# Sheet1.net
KiCad netlist of a schematic drawn in Altium Designer
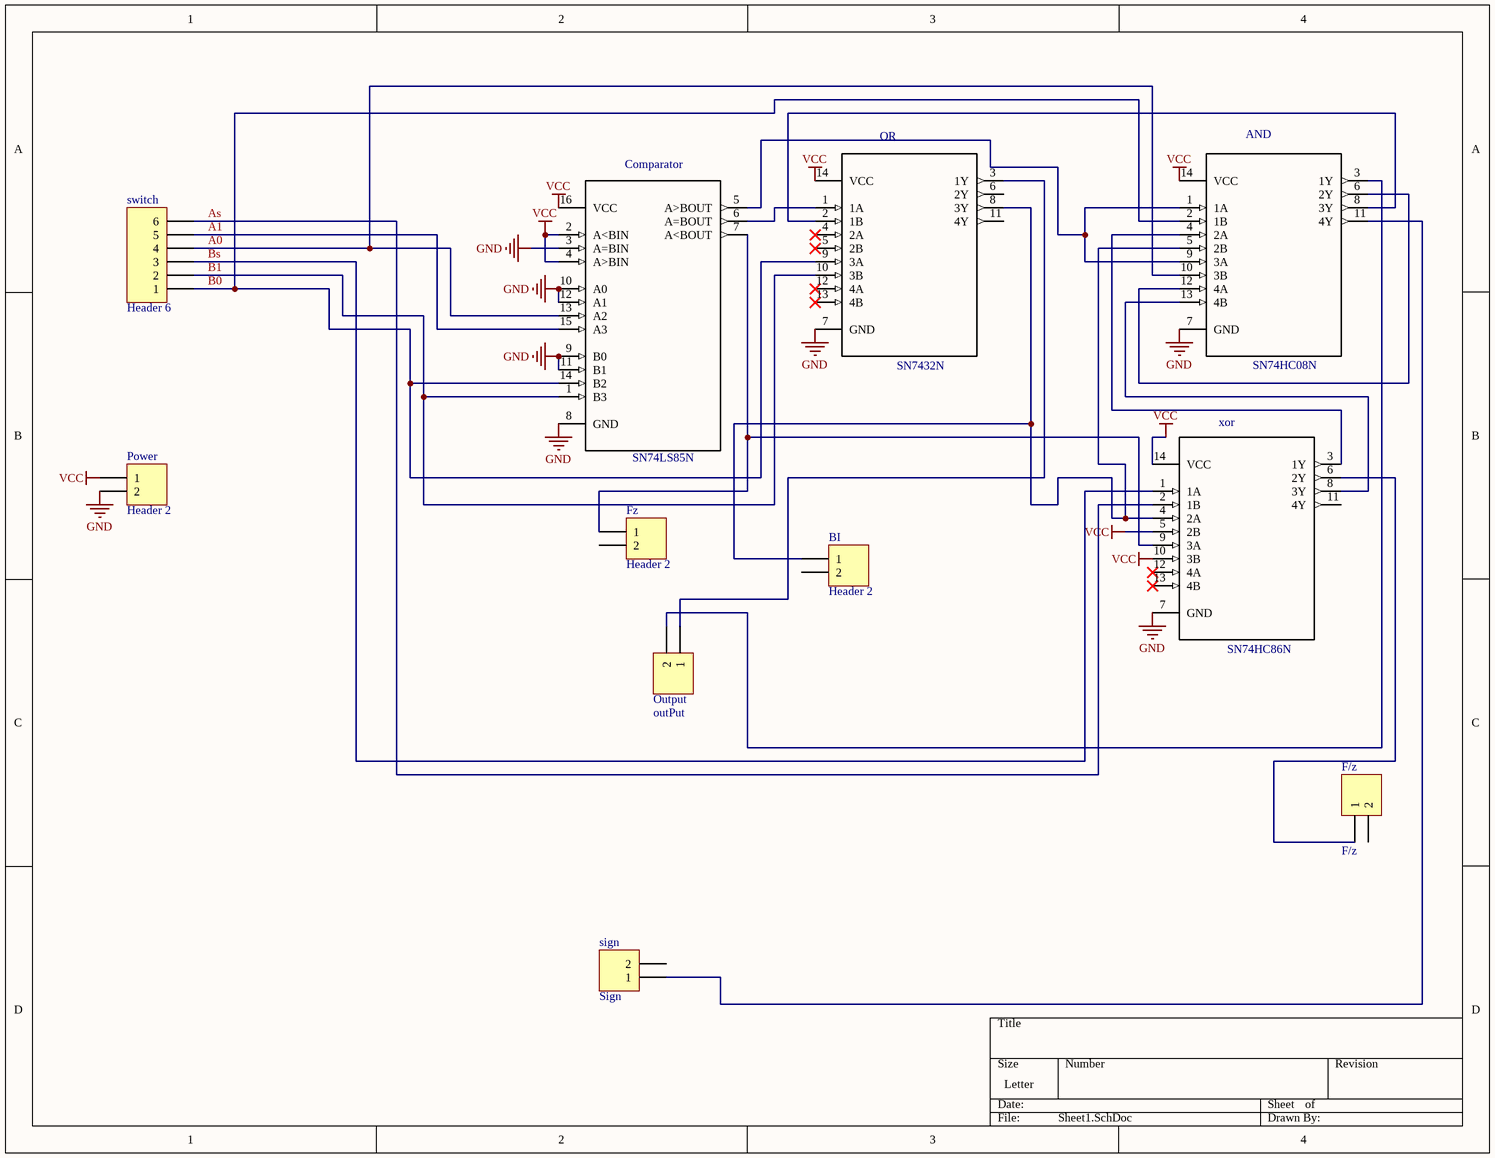
[diagram p0: Sheet1.SchDoc]

(export (version "E")
  (design (tool "Eeschema 10.0.6"))
  (components
    (comp (ref "AND")
      (value "SN74HC08N")
      (footprint "DIP254P762X508-14")
      (fields (field (name "MF") "Texas Instruments"))
      (libsource (lib "SN74HC08N") (part "SN74HC08N"))
    )
    (comp (ref "BI")
      (value "Header 2")
      (footprint "HDR1X2")
      (description "Header, 2-Pin")
      (fields (field (name "PUBLISHER") "Altium Limited"))
      (libsource (lib "Miscellaneous Connectors") (part "Header 2"))
    )
    (comp (ref "Comparator")
      (value "SN74LS85N")
      (footprint "DIP254P762X508-16")
      (description "Logic - Digital Comparators 4-bit binary or BCD Magnitude Comparator")
      (fields (field (name "MF") "Texas Instruments"))
      (libsource (lib "SN74LS85N") (part "SN74LS85N"))
    )
    (comp (ref "F/z")
      (value "F/z")
      (footprint "HDR1X2")
      (description "Header, 2-Pin")
      (fields (field (name "PUBLISHER") "Altium Limited"))
      (libsource (lib "") (part "Header 2_1"))
    )
    (comp (ref "Fz")
      (value "Header 2")
      (footprint "HDR1X2")
      (description "Header, 2-Pin")
      (fields (field (name "PUBLISHER") "Altium Limited"))
      (libsource (lib "Miscellaneous Connectors") (part "Header 2"))
    )
    (comp (ref "OR")
      (value "SN7432N")
      (footprint "DIP254P762X508-14")
      (description "OR Gate 4-Element 2-IN Bipolar 14-Pin PDIP Tube")
      (fields (field (name "MF") "Texas Instruments") (field (name "DIGI-KEY_PART_NUMBER") "296-33610-5-ND"))
      (libsource (lib "SN7432N") (part "SN7432N"))
    )
    (comp (ref "Output")
      (value "outPut")
      (footprint "HDR1X2")
      (description "Header, 2-Pin")
      (fields (field (name "PUBLISHER") "Altium Limited"))
      (libsource (lib "") (part "Header 2_2"))
    )
    (comp (ref "Power")
      (value "Header 2")
      (footprint "HDR1X2")
      (description "Header, 2-Pin")
      (fields (field (name "PUBLISHER") "Altium Limited"))
      (libsource (lib "Miscellaneous Connectors") (part "Header 2"))
    )
    (comp (ref "sign")
      (value "Sign")
      (footprint "HDR1X2")
      (description "Header, 2-Pin")
      (fields (field (name "PUBLISHER") "Altium Limited"))
      (libsource (lib "") (part "Header 2_3"))
    )
    (comp (ref "switch")
      (value "Header 6")
      (footprint "HDR1X6")
      (description "Header, 6-Pin")
      (fields (field (name "PUBLISHER") "Altium Limited"))
      (libsource (lib "Miscellaneous Connectors") (part "Header 6"))
    )
    (comp (ref "xor")
      (value "SN74HC86N")
      (footprint "DIP254P762X508-14")
      (description "IC: digital; inverter; XOR; Channels: 4; THT; DIP14; Series: HC")
      (fields (field (name "MF") "Texas Instruments"))
      (libsource (lib "SN74HC86N") (part "SN74HC86N"))
    )
  )
  (nets
    (net (code "1") (name "GND") (class "Default")
      (node (ref "AND") (pin "7") (pinfunction "GND_7") (pintype "passive"))
      (node (ref "Comparator") (pin "10") (pinfunction "A0_10") (pintype "input"))
      (node (ref "Comparator") (pin "11") (pinfunction "B1_11") (pintype "input"))
      (node (ref "Comparator") (pin "12") (pinfunction "A1_12") (pintype "input"))
      (node (ref "Comparator") (pin "3") (pinfunction "A=BIN_3") (pintype "input"))
      (node (ref "Comparator") (pin "8") (pinfunction "GND_8") (pintype "passive"))
      (node (ref "Comparator") (pin "9") (pinfunction "B0_9") (pintype "input"))
      (node (ref "OR") (pin "7") (pinfunction "GND_7") (pintype "passive"))
      (node (ref "Power") (pin "2") (pinfunction "2_2") (pintype "passive"))
      (node (ref "xor") (pin "7") (pinfunction "GND_7") (pintype "passive"))
    )
    (net (code "2") (name "Net-(AND-1A)") (class "Default")
      (node (ref "AND") (pin "1") (pinfunction "1A_1") (pintype "input"))
      (node (ref "AND") (pin "9") (pinfunction "3A_9") (pintype "input"))
      (node (ref "Comparator") (pin "5") (pinfunction "A>BOUT_5") (pintype "output"))
    )
    (net (code "3") (name "Net-(AND-1B)") (class "Default")
      (node (ref "AND") (pin "2") (pinfunction "1B_2") (pintype "input"))
      (node (ref "Comparator") (pin "14") (pinfunction "B2_14") (pintype "input"))
      (node (ref "OR") (pin "9") (pinfunction "3A_9") (pintype "input"))
      (node (ref "switch") (pin "1") (pinfunction "1_1") (pintype "passive"))
    )
    (net (code "4") (name "Net-(AND-1Y)") (class "Default")
      (node (ref "AND") (pin "3") (pinfunction "1Y_3") (pintype "output"))
      (node (ref "Output") (pin "2") (pinfunction "2_2") (pintype "passive"))
    )
    (net (code "5") (name "Net-(AND-2A)") (class "Default")
      (node (ref "AND") (pin "4") (pinfunction "2A_4") (pintype "input"))
      (node (ref "xor") (pin "3") (pinfunction "1Y_3") (pintype "output"))
    )
    (net (code "6") (name "Net-(AND-2B)") (class "Default")
      (node (ref "AND") (pin "5") (pinfunction "2B_5") (pintype "input"))
      (node (ref "BI") (pin "1") (pinfunction "1_1") (pintype "passive"))
      (node (ref "OR") (pin "8") (pinfunction "3Y_8") (pintype "output"))
      (node (ref "xor") (pin "4") (pinfunction "2A_4") (pintype "input"))
    )
    (net (code "7") (name "Net-(AND-2Y)") (class "Default")
      (node (ref "AND") (pin "12") (pinfunction "4A_12") (pintype "input"))
      (node (ref "AND") (pin "6") (pinfunction "2Y_6") (pintype "output"))
    )
    (net (code "8") (name "Net-(AND-3B)") (class "Default")
      (node (ref "AND") (pin "10") (pinfunction "3B_10") (pintype "input"))
      (node (ref "Comparator") (pin "13") (pinfunction "A2_13") (pintype "input"))
      (node (ref "switch") (pin "4") (pinfunction "4_4") (pintype "passive"))
    )
    (net (code "9") (name "Net-(AND-3Y)") (class "Default")
      (node (ref "AND") (pin "8") (pinfunction "3Y_8") (pintype "output"))
      (node (ref "OR") (pin "2") (pinfunction "1B_2") (pintype "input"))
    )
    (net (code "10") (name "Net-(AND-4B)") (class "Default")
      (node (ref "AND") (pin "13") (pinfunction "4B_13") (pintype "input"))
      (node (ref "xor") (pin "8") (pinfunction "3Y_8") (pintype "output"))
    )
    (net (code "11") (name "Net-(AND-4Y)") (class "Default")
      (node (ref "AND") (pin "11") (pinfunction "4Y_11") (pintype "output"))
      (node (ref "sign") (pin "1") (pinfunction "1_1") (pintype "passive"))
    )
    (net (code "12") (name "Net-(Comparator-A3)") (class "Default")
      (node (ref "Comparator") (pin "15") (pinfunction "A3_15") (pintype "input"))
      (node (ref "switch") (pin "5") (pinfunction "5_5") (pintype "passive"))
    )
    (net (code "13") (name "Net-(Comparator-A<BOUT)") (class "Default")
      (node (ref "Comparator") (pin "7") (pinfunction "A<BOUT_7") (pintype "output"))
      (node (ref "Fz") (pin "1") (pinfunction "1_1") (pintype "passive"))
      (node (ref "xor") (pin "9") (pinfunction "3A_9") (pintype "input"))
    )
    (net (code "14") (name "Net-(Comparator-A=BOUT)") (class "Default")
      (node (ref "Comparator") (pin "6") (pinfunction "A=BOUT_6") (pintype "output"))
      (node (ref "OR") (pin "1") (pinfunction "1A_1") (pintype "input"))
    )
    (net (code "15") (name "Net-(Comparator-B3)") (class "Default")
      (node (ref "Comparator") (pin "1") (pinfunction "B3_1") (pintype "input"))
      (node (ref "OR") (pin "10") (pinfunction "3B_10") (pintype "input"))
      (node (ref "switch") (pin "2") (pinfunction "2_2") (pintype "passive"))
    )
    (net (code "16") (name "Net-(OR-1Y)") (class "Default")
      (node (ref "OR") (pin "3") (pinfunction "1Y_3") (pintype "output"))
      (node (ref "Output") (pin "1") (pinfunction "1_1") (pintype "passive"))
    )
    (net (code "17") (name "Net-(xor-1A)") (class "Default")
      (node (ref "switch") (pin "3") (pinfunction "3_3") (pintype "passive"))
      (node (ref "xor") (pin "1") (pinfunction "1A_1") (pintype "input"))
    )
    (net (code "18") (name "Net-(xor-1B)") (class "Default")
      (node (ref "switch") (pin "6") (pinfunction "6_6") (pintype "passive"))
      (node (ref "xor") (pin "2") (pinfunction "1B_2") (pintype "input"))
    )
    (net (code "19") (name "Net-(xor-2Y)") (class "Default")
      (node (ref "F/z") (pin "1") (pinfunction "1_1") (pintype "passive"))
      (node (ref "xor") (pin "6") (pinfunction "2Y_6") (pintype "output"))
    )
    (net (code "20") (name "VCC") (class "Default")
      (node (ref "AND") (pin "14") (pinfunction "VCC_14") (pintype "power_in"))
      (node (ref "Comparator") (pin "16") (pinfunction "VCC_16") (pintype "power_in"))
      (node (ref "Comparator") (pin "2") (pinfunction "A<BIN_2") (pintype "input"))
      (node (ref "Comparator") (pin "4") (pinfunction "A>BIN_4") (pintype "input"))
      (node (ref "OR") (pin "14") (pinfunction "VCC_14") (pintype "power_in"))
      (node (ref "Power") (pin "1") (pinfunction "1_1") (pintype "passive"))
      (node (ref "xor") (pin "10") (pinfunction "3B_10") (pintype "input"))
      (node (ref "xor") (pin "14") (pinfunction "VCC_14") (pintype "power_in"))
      (node (ref "xor") (pin "5") (pinfunction "2B_5") (pintype "input"))
    )
    (net (code "21") (name "unconnected-(BI-Pad2)") (class "Default")
      (node (ref "BI") (pin "2") (pinfunction "2_2") (pintype "passive"))
    )
    (net (code "22") (name "unconnected-(F/z-Pad2)") (class "Default")
      (node (ref "F/z") (pin "2") (pinfunction "2_2") (pintype "passive"))
    )
    (net (code "23") (name "unconnected-(Fz-Pad2)") (class "Default")
      (node (ref "Fz") (pin "2") (pinfunction "2_2") (pintype "passive"))
    )
    (net (code "24") (name "unconnected-(OR-2A-Pad4)") (class "Default")
      (node (ref "OR") (pin "4") (pinfunction "2A_4") (pintype "input+no_connect"))
    )
    (net (code "25") (name "unconnected-(OR-2B-Pad5)") (class "Default")
      (node (ref "OR") (pin "5") (pinfunction "2B_5") (pintype "input+no_connect"))
    )
    (net (code "26") (name "unconnected-(OR-2Y-Pad6)") (class "Default")
      (node (ref "OR") (pin "6") (pinfunction "2Y_6") (pintype "output"))
    )
    (net (code "27") (name "unconnected-(OR-4A-Pad12)") (class "Default")
      (node (ref "OR") (pin "12") (pinfunction "4A_12") (pintype "input+no_connect"))
    )
    (net (code "28") (name "unconnected-(OR-4B-Pad13)") (class "Default")
      (node (ref "OR") (pin "13") (pinfunction "4B_13") (pintype "input+no_connect"))
    )
    (net (code "29") (name "unconnected-(OR-4Y-Pad11)") (class "Default")
      (node (ref "OR") (pin "11") (pinfunction "4Y_11") (pintype "output"))
    )
    (net (code "30") (name "unconnected-(sign-Pad2)") (class "Default")
      (node (ref "sign") (pin "2") (pinfunction "2_2") (pintype "passive"))
    )
    (net (code "31") (name "unconnected-(xor-4A-Pad12)") (class "Default")
      (node (ref "xor") (pin "12") (pinfunction "4A_12") (pintype "input+no_connect"))
    )
    (net (code "32") (name "unconnected-(xor-4B-Pad13)") (class "Default")
      (node (ref "xor") (pin "13") (pinfunction "4B_13") (pintype "input+no_connect"))
    )
    (net (code "33") (name "unconnected-(xor-4Y-Pad11)") (class "Default")
      (node (ref "xor") (pin "11") (pinfunction "4Y_11") (pintype "output"))
    )
  )
)
